# Schematic.net
KiCad netlist of a schematic drawn in Altium Designer
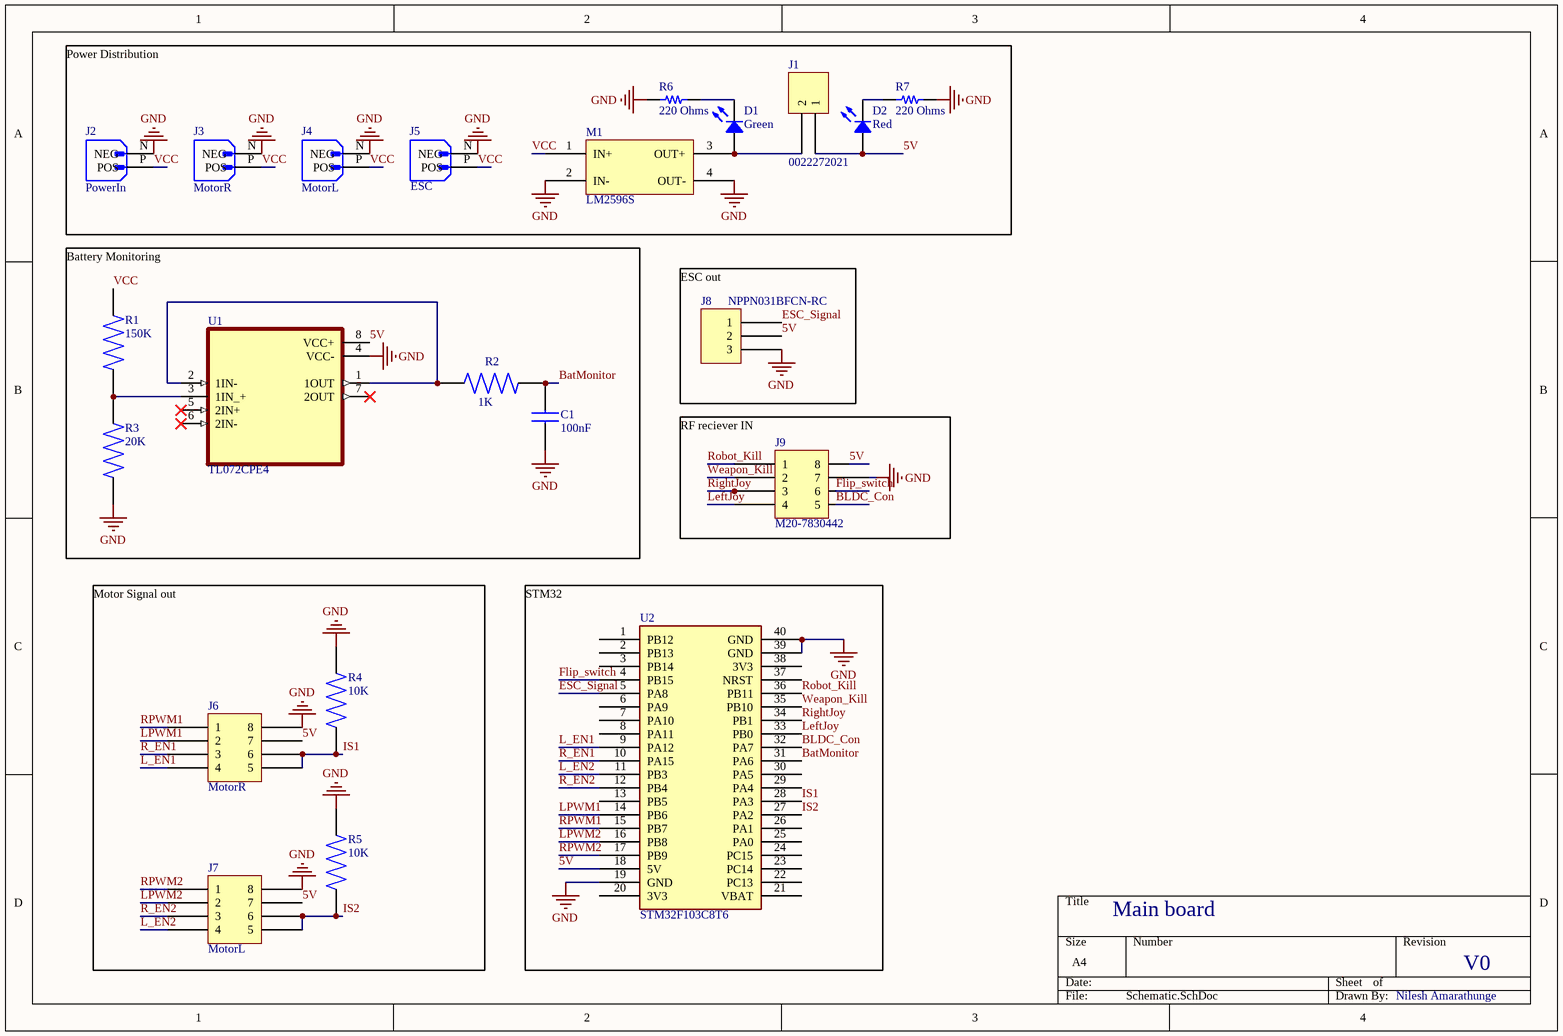
[diagram p0: Schematic.SchDoc]

(export (version "E")
  (design (tool "Eeschema 10.0.6"))
  (components
    (comp (ref "C1")
      (value "100nF")
      (footprint "C320C")
      (fields (field (name "MF") "KEMET") (field (name "MP") "C320C104M5U5TA"))
      (libsource (lib "C320C104M5U5TA") (part "C320C104M5U5TA"))
    )
    (comp (ref "D1")
      (value "Green")
      (footprint "LED 0805_2012 GREEN")
      (description "LED GREEN CLEAR 2SMD")
      (fields (field (name "PART NUMBER") "APHCM2012ZGC/G-F01") (field (name "MANUFACTURER") "Kingbright"))
      (libsource (lib "Celestial Altium Library - altium_library") (part "LED"))
    )
    (comp (ref "D2")
      (value "Red")
      (footprint "LED 0805_2012 RED")
      (description "LED RED 0805 SMD")
      (fields (field (name "PART NUMBER") "5990110007F") (field (name "MANUFACTURER") "Dialight"))
      (libsource (lib "Celestial Altium Library - altium_library") (part "LED"))
    )
    (comp (ref "J1")
      (value "0022272021")
      (footprint "MOLEX KK 0022272021")
      (description "CONN HEADER VERT 2POS 2.54MM")
      (fields (field (name "MANUFACTURER") "Molex"))
      (libsource (lib "Celestial Altium Library - altium_library") (part "2 Pin"))
    )
    (comp (ref "J2")
      (value "PowerIn")
      (footprint "AMASS_XT60-M")
      (description "Plug; DC supply; XT60; male; PIN: 2; for cable; soldered; 30A; 500V")
      (fields (field (name "MF") "AMASS") (field (name "MP") "XT60-M"))
      (libsource (lib "XT60-M") (part "XT60-M"))
    )
    (comp (ref "J3")
      (value "MotorR")
      (footprint "AMASS_XT60-M")
      (description "Plug; DC supply; XT60; male; PIN: 2; for cable; soldered; 30A; 500V")
      (fields (field (name "MF") "AMASS") (field (name "MP") "XT60-M"))
      (libsource (lib "XT60-M") (part "XT60-M"))
    )
    (comp (ref "J4")
      (value "MotorL")
      (footprint "AMASS_XT60-M")
      (description "Plug; DC supply; XT60; male; PIN: 2; for cable; soldered; 30A; 500V")
      (fields (field (name "MF") "AMASS") (field (name "MP") "XT60-M"))
      (libsource (lib "XT60-M") (part "XT60-M"))
    )
    (comp (ref "J5")
      (value "ESC")
      (footprint "AMASS_XT60-M")
      (description "Plug; DC supply; XT60; male; PIN: 2; for cable; soldered; 30A; 500V")
      (fields (field (name "MF") "AMASS") (field (name "MP") "XT60-M"))
      (libsource (lib "XT60-M") (part "XT60-M"))
    )
    (comp (ref "J6")
      (value "MotorR")
      (footprint "HARWIN M20-7830445")
      (description "CONN RCPT 8POS 0.1 GOLD PCB")
      (fields (field (name "PART NUMBER") "M20-7830442") (field (name "MANUFACTURER") "Harwin Inc."))
      (libsource (lib "Celestial Altium Library - altium_library") (part "2X4 PIN DU"))
    )
    (comp (ref "J7")
      (value "MotorL")
      (footprint "HARWIN M20-7830445")
      (description "CONN RCPT 8POS 0.1 GOLD PCB")
      (fields (field (name "PART NUMBER") "M20-7830442") (field (name "MANUFACTURER") "Harwin Inc."))
      (libsource (lib "Celestial Altium Library - altium_library") (part "2X4 PIN DU"))
    )
    (comp (ref "J8")
      (value "NPPN031BFCN-RC")
      (footprint "SULLINS NPPN031BFCN")
      (description "CONN HDR 3POS 0.079 GOLD PCB")
      (fields (field (name "MANUFACTURER") "Sullins Connector Solutions"))
      (libsource (lib "Celestial Altium Library - altium_library") (part "3 Pin"))
    )
    (comp (ref "J9")
      (value "M20-7830442")
      (footprint "HARWIN M20-7830445")
      (description "CONN RCPT 8POS 0.1 GOLD PCB")
      (fields (field (name "MANUFACTURER") "Harwin Inc."))
      (libsource (lib "Celestial Altium Library - altium_library") (part "2X4 PIN DU"))
    )
    (comp (ref "M1") (value "LM2596S") (footprint "LM2596S") (libsource (lib "LM2596S") (part "LM2596S")))
    (comp (ref "R1")
      (value "150K")
      (footprint "RESAD1869W81L1270D457")
      (fields (field (name "MP") "ALSR0310K00FE12"))
      (libsource (lib "ALSR0310K00FE12") (part "ALSR0310K00FE12"))
    )
    (comp (ref "R2")
      (value "1K")
      (footprint "RESAD1869W81L1270D457")
      (fields (field (name "MP") "ALSR0310K00FE12"))
      (libsource (lib "ALSR0310K00FE12") (part "ALSR0310K00FE12"))
    )
    (comp (ref "R3")
      (value "20K")
      (footprint "RESAD1869W81L1270D457")
      (fields (field (name "MP") "ALSR0310K00FE12"))
      (libsource (lib "ALSR0310K00FE12") (part "ALSR0310K00FE12"))
    )
    (comp (ref "R4")
      (value "10K")
      (footprint "RESAD1869W81L1270D457")
      (fields (field (name "MP") "ALSR0310K00FE12"))
      (libsource (lib "ALSR0310K00FE12") (part "ALSR0310K00FE12"))
    )
    (comp (ref "R5")
      (value "10K")
      (footprint "RESAD1869W81L1270D457")
      (fields (field (name "MP") "ALSR0310K00FE12"))
      (libsource (lib "ALSR0310K00FE12") (part "ALSR0310K00FE12"))
    )
    (comp (ref "R6")
      (value "220 Ohms")
      (footprint "RES 0805_2012")
      (description "RES SMD 220 OHM 1% 0.4W 0805")
      (fields (field (name "PART NUMBER") "ESR10EZPF2200") (field (name "MANUFACTURER") "Rohm Semiconductor"))
      (libsource (lib "Celestial Altium Library - altium_library") (part "Resistor"))
    )
    (comp (ref "R7")
      (value "220 Ohms")
      (footprint "RES 0805_2012")
      (description "RES SMD 220 OHM 1% 0.4W 0805")
      (fields (field (name "PART NUMBER") "ESR10EZPF2200") (field (name "MANUFACTURER") "Rohm Semiconductor"))
      (libsource (lib "Celestial Altium Library - altium_library") (part "Resistor"))
    )
    (comp (ref "U1")
      (value "TL072CPE4")
      (footprint "DIP794W45P254L959H508Q8")
      (description "Dual Low-Noise JFET-Input General-Purpose Operational Amplifier 8-PDIP 0 to 70")
      (fields (field (name "MF") "Texas Instruments"))
      (libsource (lib "TL072CPE4") (part "TL072CPE4"))
    )
    (comp (ref "U2")
      (value "STM32F103C8T6")
      (footprint "Stm32 BluePill")
      (description "Designed By @Alixahedi")
      (libsource (lib "Stm32 Blue Pill") (part "BluePill"))
    )
  )
  (nets
    (net (code "1") (name "/5V") (class "Default")
      (node (ref "D2") (pin "1") (pinfunction "1_1") (pintype "passive"))
      (node (ref "J1") (pin "1") (pinfunction "1_1") (pintype "passive"))
      (node (ref "J6") (pin "7") (pinfunction "7_7") (pintype "passive"))
      (node (ref "J7") (pin "7") (pinfunction "7_7") (pintype "passive"))
      (node (ref "J8") (pin "2") (pinfunction "2_2") (pintype "passive"))
      (node (ref "J9") (pin "8") (pinfunction "8_8") (pintype "passive"))
      (node (ref "U1") (pin "8") (pinfunction "VCC+_8") (pintype "power_in"))
      (node (ref "U2") (pin "18") (pinfunction "5V_18") (pintype "passive"))
    )
    (net (code "2") (name "/BLDC_Con") (class "Default")
      (node (ref "J9") (pin "5") (pinfunction "5_5") (pintype "passive"))
      (node (ref "U2") (pin "32") (pinfunction "PA7_32") (pintype "passive"))
    )
    (net (code "3") (name "/BatMonitor") (class "Default")
      (node (ref "C1") (pin "2") (pinfunction "2_2") (pintype "passive"))
      (node (ref "R2") (pin "1") (pinfunction "1_1") (pintype "passive"))
      (node (ref "U2") (pin "31") (pinfunction "PA6_31") (pintype "passive"))
    )
    (net (code "4") (name "/ESC_Signal") (class "Default")
      (node (ref "J8") (pin "1") (pinfunction "1_1") (pintype "passive"))
      (node (ref "U2") (pin "5") (pinfunction "PA8_5") (pintype "passive"))
    )
    (net (code "5") (name "/Flip_switch") (class "Default")
      (node (ref "J9") (pin "6") (pinfunction "6_6") (pintype "passive"))
      (node (ref "U2") (pin "4") (pinfunction "PB15_4") (pintype "passive"))
    )
    (net (code "6") (name "/IS1") (class "Default")
      (node (ref "J6") (pin "5") (pinfunction "5_5") (pintype "passive"))
      (node (ref "J6") (pin "6") (pinfunction "6_6") (pintype "passive"))
      (node (ref "R4") (pin "2") (pinfunction "2_2") (pintype "passive"))
      (node (ref "U2") (pin "28") (pinfunction "PA3_28") (pintype "passive"))
    )
    (net (code "7") (name "/IS2") (class "Default")
      (node (ref "J7") (pin "5") (pinfunction "5_5") (pintype "passive"))
      (node (ref "J7") (pin "6") (pinfunction "6_6") (pintype "passive"))
      (node (ref "R5") (pin "2") (pinfunction "2_2") (pintype "passive"))
      (node (ref "U2") (pin "27") (pinfunction "PA2_27") (pintype "passive"))
    )
    (net (code "8") (name "/LPWM1") (class "Default")
      (node (ref "J6") (pin "2") (pinfunction "2_2") (pintype "passive"))
      (node (ref "U2") (pin "14") (pinfunction "PB6_14") (pintype "passive"))
    )
    (net (code "9") (name "/LPWM2") (class "Default")
      (node (ref "J7") (pin "2") (pinfunction "2_2") (pintype "passive"))
      (node (ref "U2") (pin "16") (pinfunction "PB8_16") (pintype "passive"))
    )
    (net (code "10") (name "/L_EN1") (class "Default")
      (node (ref "J6") (pin "4") (pinfunction "4_4") (pintype "passive"))
      (node (ref "U2") (pin "9") (pinfunction "PA12_9") (pintype "passive"))
    )
    (net (code "11") (name "/L_EN2") (class "Default")
      (node (ref "J7") (pin "4") (pinfunction "4_4") (pintype "passive"))
      (node (ref "U2") (pin "11") (pinfunction "PB3_11") (pintype "passive"))
    )
    (net (code "12") (name "/LeftJoy") (class "Default")
      (node (ref "J9") (pin "4") (pinfunction "4_4") (pintype "passive"))
      (node (ref "U2") (pin "33") (pinfunction "PB0_33") (pintype "passive"))
    )
    (net (code "13") (name "/RPWM1") (class "Default")
      (node (ref "J6") (pin "1") (pinfunction "1_1") (pintype "passive"))
      (node (ref "U2") (pin "15") (pinfunction "PB7_15") (pintype "passive"))
    )
    (net (code "14") (name "/RPWM2") (class "Default")
      (node (ref "J7") (pin "1") (pinfunction "1_1") (pintype "passive"))
      (node (ref "U2") (pin "17") (pinfunction "PB9_17") (pintype "passive"))
    )
    (net (code "15") (name "/R_EN1") (class "Default")
      (node (ref "J6") (pin "3") (pinfunction "3_3") (pintype "passive"))
      (node (ref "U2") (pin "10") (pinfunction "PA15_10") (pintype "passive"))
    )
    (net (code "16") (name "/R_EN2") (class "Default")
      (node (ref "J7") (pin "3") (pinfunction "3_3") (pintype "passive"))
      (node (ref "U2") (pin "12") (pinfunction "PB4_12") (pintype "passive"))
    )
    (net (code "17") (name "/RightJoy") (class "Default")
      (node (ref "J9") (pin "3") (pinfunction "3_3") (pintype "passive"))
      (node (ref "U2") (pin "34") (pinfunction "PB1_34") (pintype "passive"))
    )
    (net (code "18") (name "/Robot_Kill") (class "Default")
      (node (ref "J9") (pin "1") (pinfunction "1_1") (pintype "passive"))
      (node (ref "U2") (pin "36") (pinfunction "PB11_36") (pintype "passive"))
    )
    (net (code "19") (name "/VCC") (class "Default")
      (node (ref "J2") (pin "P") (pinfunction "POS_P") (pintype "passive"))
      (node (ref "J3") (pin "P") (pinfunction "POS_P") (pintype "passive"))
      (node (ref "J4") (pin "P") (pinfunction "POS_P") (pintype "passive"))
      (node (ref "J5") (pin "P") (pinfunction "POS_P") (pintype "passive"))
      (node (ref "M1") (pin "1") (pinfunction "IN+_1") (pintype "passive"))
      (node (ref "R1") (pin "2") (pinfunction "2_2") (pintype "passive"))
    )
    (net (code "20") (name "/Weapon_Kill") (class "Default")
      (node (ref "J9") (pin "2") (pinfunction "2_2") (pintype "passive"))
      (node (ref "U2") (pin "35") (pinfunction "PB10_35") (pintype "passive"))
    )
    (net (code "21") (name "GND") (class "Default")
      (node (ref "C1") (pin "1") (pinfunction "1_1") (pintype "passive"))
      (node (ref "J2") (pin "N") (pinfunction "NEG_N") (pintype "passive"))
      (node (ref "J3") (pin "N") (pinfunction "NEG_N") (pintype "passive"))
      (node (ref "J4") (pin "N") (pinfunction "NEG_N") (pintype "passive"))
      (node (ref "J5") (pin "N") (pinfunction "NEG_N") (pintype "passive"))
      (node (ref "J6") (pin "8") (pinfunction "8_8") (pintype "passive"))
      (node (ref "J7") (pin "8") (pinfunction "8_8") (pintype "passive"))
      (node (ref "J8") (pin "3") (pinfunction "3_3") (pintype "passive"))
      (node (ref "J9") (pin "7") (pinfunction "7_7") (pintype "passive"))
      (node (ref "M1") (pin "2") (pinfunction "IN-_2") (pintype "passive"))
      (node (ref "M1") (pin "4") (pinfunction "OUT-_4") (pintype "passive"))
      (node (ref "R3") (pin "1") (pinfunction "1_1") (pintype "passive"))
      (node (ref "R4") (pin "1") (pinfunction "1_1") (pintype "passive"))
      (node (ref "R5") (pin "1") (pinfunction "1_1") (pintype "passive"))
      (node (ref "R6") (pin "1") (pinfunction "1_1") (pintype "passive"))
      (node (ref "R7") (pin "2") (pinfunction "2_2") (pintype "passive"))
      (node (ref "U1") (pin "4") (pinfunction "VCC-_4") (pintype "power_in"))
      (node (ref "U2") (pin "19") (pinfunction "GND_19") (pintype "passive"))
      (node (ref "U2") (pin "39") (pinfunction "GND_39") (pintype "passive"))
      (node (ref "U2") (pin "40") (pinfunction "GND_40") (pintype "passive"))
    )
    (net (code "22") (name "Net-(D1-Pad2)") (class "Default")
      (node (ref "D1") (pin "2") (pinfunction "2_2") (pintype "passive"))
      (node (ref "R6") (pin "2") (pinfunction "2_2") (pintype "passive"))
    )
    (net (code "23") (name "Net-(D2-Pad2)") (class "Default")
      (node (ref "D2") (pin "2") (pinfunction "2_2") (pintype "passive"))
      (node (ref "R7") (pin "1") (pinfunction "1_1") (pintype "passive"))
    )
    (net (code "24") (name "Net-(M1-OUT+)") (class "Default")
      (node (ref "D1") (pin "1") (pinfunction "1_1") (pintype "passive"))
      (node (ref "J1") (pin "2") (pinfunction "2_2") (pintype "passive"))
      (node (ref "M1") (pin "3") (pinfunction "OUT+_3") (pintype "passive"))
    )
    (net (code "25") (name "Net-(U1-1IN-)") (class "Default")
      (node (ref "R2") (pin "2") (pinfunction "2_2") (pintype "passive"))
      (node (ref "U1") (pin "1") (pinfunction "1OUT_1") (pintype "output"))
      (node (ref "U1") (pin "2") (pinfunction "1IN-_2") (pintype "input"))
    )
    (net (code "26") (name "Net-(U1-1IN_+)") (class "Default")
      (node (ref "R1") (pin "1") (pinfunction "1_1") (pintype "passive"))
      (node (ref "R3") (pin "2") (pinfunction "2_2") (pintype "passive"))
      (node (ref "U1") (pin "3") (pinfunction "1IN_+_3") (pintype "passive"))
    )
    (net (code "27") (name "unconnected-(U1-2IN+-Pad5)") (class "Default")
      (node (ref "U1") (pin "5") (pinfunction "2IN+_5") (pintype "input+no_connect"))
    )
    (net (code "28") (name "unconnected-(U1-2IN--Pad6)") (class "Default")
      (node (ref "U1") (pin "6") (pinfunction "2IN-_6") (pintype "input+no_connect"))
    )
    (net (code "29") (name "unconnected-(U1-2OUT-Pad7)") (class "Default")
      (node (ref "U1") (pin "7") (pinfunction "2OUT_7") (pintype "output+no_connect"))
    )
    (net (code "30") (name "unconnected-(U2-3V3-Pad20)") (class "Default")
      (node (ref "U2") (pin "20") (pinfunction "3V3_20") (pintype "passive"))
    )
    (net (code "31") (name "unconnected-(U2-3V3-Pad38)") (class "Default")
      (node (ref "U2") (pin "38") (pinfunction "3V3_38") (pintype "passive"))
    )
    (net (code "32") (name "unconnected-(U2-NRST-Pad37)") (class "Default")
      (node (ref "U2") (pin "37") (pinfunction "NRST_37") (pintype "passive"))
    )
    (net (code "33") (name "unconnected-(U2-PA0-Pad25)") (class "Default")
      (node (ref "U2") (pin "25") (pinfunction "PA0_25") (pintype "passive"))
    )
    (net (code "34") (name "unconnected-(U2-PA1-Pad26)") (class "Default")
      (node (ref "U2") (pin "26") (pinfunction "PA1_26") (pintype "passive"))
    )
    (net (code "35") (name "unconnected-(U2-PA4-Pad29)") (class "Default")
      (node (ref "U2") (pin "29") (pinfunction "PA4_29") (pintype "passive"))
    )
    (net (code "36") (name "unconnected-(U2-PA5-Pad30)") (class "Default")
      (node (ref "U2") (pin "30") (pinfunction "PA5_30") (pintype "passive"))
    )
    (net (code "37") (name "unconnected-(U2-PA9-Pad6)") (class "Default")
      (node (ref "U2") (pin "6") (pinfunction "PA9_6") (pintype "passive"))
    )
    (net (code "38") (name "unconnected-(U2-PA10-Pad7)") (class "Default")
      (node (ref "U2") (pin "7") (pinfunction "PA10_7") (pintype "passive"))
    )
    (net (code "39") (name "unconnected-(U2-PA11-Pad8)") (class "Default")
      (node (ref "U2") (pin "8") (pinfunction "PA11_8") (pintype "passive"))
    )
    (net (code "40") (name "unconnected-(U2-PB5-Pad13)") (class "Default")
      (node (ref "U2") (pin "13") (pinfunction "PB5_13") (pintype "passive"))
    )
    (net (code "41") (name "unconnected-(U2-PB12-Pad1)") (class "Default")
      (node (ref "U2") (pin "1") (pinfunction "PB12_1") (pintype "passive"))
    )
    (net (code "42") (name "unconnected-(U2-PB13-Pad2)") (class "Default")
      (node (ref "U2") (pin "2") (pinfunction "PB13_2") (pintype "passive"))
    )
    (net (code "43") (name "unconnected-(U2-PB14-Pad3)") (class "Default")
      (node (ref "U2") (pin "3") (pinfunction "PB14_3") (pintype "passive"))
    )
    (net (code "44") (name "unconnected-(U2-PC13-Pad22)") (class "Default")
      (node (ref "U2") (pin "22") (pinfunction "PC13_22") (pintype "passive"))
    )
    (net (code "45") (name "unconnected-(U2-PC14-Pad23)") (class "Default")
      (node (ref "U2") (pin "23") (pinfunction "PC14_23") (pintype "passive"))
    )
    (net (code "46") (name "unconnected-(U2-PC15-Pad24)") (class "Default")
      (node (ref "U2") (pin "24") (pinfunction "PC15_24") (pintype "passive"))
    )
    (net (code "47") (name "unconnected-(U2-VBAT-Pad21)") (class "Default")
      (node (ref "U2") (pin "21") (pinfunction "VBAT_21") (pintype "passive"))
    )
  )
)
